# schematic.net
KiCad netlist of a schematic drawn in EAGLE
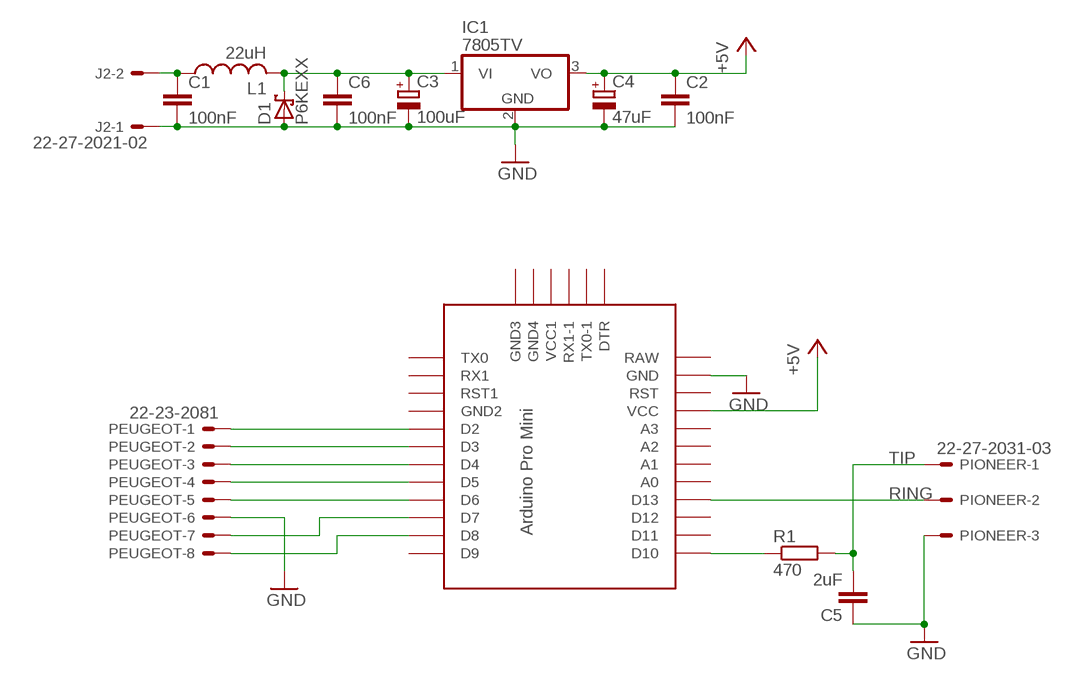
[diagram p0: schematic, sheet 1]

(export (version "E")
  (design (tool "Eeschema 10.0.6"))
  (components
    (comp (ref "C1")
      (value "100nF")
      (footprint "eagle-import:C025-024X044")
      (libsource (lib "eagle-import") (part "C-EU025-024X044"))
    )
    (comp (ref "C2")
      (value "100nF")
      (footprint "eagle-import:C025-024X044")
      (libsource (lib "eagle-import") (part "C-EU025-024X044"))
    )
    (comp (ref "C3")
      (value "100uF")
      (footprint "eagle-import:085CS_1AR")
      (libsource (lib "eagle-import") (part "CPOL-EU085CS-1AR"))
    )
    (comp (ref "C4")
      (value "47uF")
      (footprint "eagle-import:085CS_1AR")
      (libsource (lib "eagle-import") (part "CPOL-EU085CS-1AR"))
    )
    (comp (ref "C5")
      (value "2uF")
      (footprint "eagle-import:C025-024X044")
      (libsource (lib "eagle-import") (part "C-EU025-024X044"))
    )
    (comp (ref "C6")
      (value "100nF")
      (footprint "eagle-import:C025-024X044")
      (libsource (lib "eagle-import") (part "C-EU025-024X044"))
    )
    (comp (ref "D1")
      (value "P6KEXX")
      (footprint "eagle-import:CB417-15")
      (libsource (lib "eagle-import") (part "P6KEXX"))
    )
    (comp (ref "IC1")
      (value "7805TV")
      (footprint "eagle-import:TO220V")
      (libsource (lib "eagle-import") (part "78TV05"))
    )
    (comp (ref "J2")
      (value "22-27-2021-02")
      (footprint "eagle-import:6410-02")
      (libsource (lib "eagle-import") (part "22-?-0227-2021"))
    )
    (comp (ref "L1")
      (value "22uH")
      (footprint "eagle-import:0204_5")
      (libsource (lib "eagle-import") (part "L-US0204/5"))
    )
    (comp (ref "PEUGEOT")
      (value "22-23-2081")
      (footprint "eagle-import:22-23-2081")
      (fields (field (name "MF") "MOLEX"))
      (libsource (lib "eagle-import") (part "22-23-2081"))
    )
    (comp (ref "PIONEER")
      (value "22-27-2031-03")
      (footprint "eagle-import:6410-03")
      (libsource (lib "eagle-import") (part "22-?-0327-2031"))
    )
    (comp (ref "R1")
      (value "470")
      (footprint "eagle-import:0204V")
      (libsource (lib "eagle-import") (part "R-EU_0204/2V"))
    )
    (comp (ref "U$3")
      (value "PRO-MINI-2")
      (footprint "eagle-import:PRO-MINI-2")
      (libsource (lib "eagle-import") (part "PRO-MINI-2"))
    )
  )
  (nets
    (net (code "1") (name "+5V") (class "Default")
      (node (ref "C2") (pin "1") (pinfunction "1_1") (pintype "passive"))
      (node (ref "C4") (pin "+") (pinfunction "+_+") (pintype "passive"))
      (node (ref "IC1") (pin "3") (pinfunction "VO_3") (pintype "passive"))
      (node (ref "U$3") (pin "VCC") (pinfunction "VCC_VCC") (pintype "bidirectional"))
    )
    (net (code "2") (name "/RING") (class "Default")
      (node (ref "PIONEER") (pin "2") (pinfunction "S_2") (pintype "passive"))
      (node (ref "U$3") (pin "D13") (pinfunction "D13_D13") (pintype "bidirectional"))
    )
    (net (code "3") (name "/TIP") (class "Default")
      (node (ref "C5") (pin "2") (pinfunction "2_2") (pintype "passive"))
      (node (ref "PIONEER") (pin "1") (pinfunction "S_1") (pintype "passive"))
      (node (ref "R1") (pin "2") (pinfunction "2_2") (pintype "passive"))
    )
    (net (code "4") (name "GND") (class "Default")
      (node (ref "C1") (pin "2") (pinfunction "2_2") (pintype "passive"))
      (node (ref "C2") (pin "2") (pinfunction "2_2") (pintype "passive"))
      (node (ref "C3") (pin "-") (pinfunction "-_-") (pintype "passive"))
      (node (ref "C4") (pin "-") (pinfunction "-_-") (pintype "passive"))
      (node (ref "C5") (pin "1") (pinfunction "1_1") (pintype "passive"))
      (node (ref "C6") (pin "2") (pinfunction "2_2") (pintype "passive"))
      (node (ref "D1") (pin "A") (pinfunction "A_A") (pintype "passive"))
      (node (ref "IC1") (pin "2") (pinfunction "GND_2") (pintype "passive"))
      (node (ref "J2") (pin "1") (pinfunction "S_1") (pintype "passive"))
      (node (ref "PEUGEOT") (pin "6") (pinfunction "S_6") (pintype "passive"))
      (node (ref "PIONEER") (pin "3") (pinfunction "S_3") (pintype "passive"))
      (node (ref "U$3") (pin "GND") (pinfunction "GND_GND") (pintype "bidirectional"))
    )
    (net (code "5") (name "Net-(IC1-VI)") (class "Default")
      (node (ref "C3") (pin "+") (pinfunction "+_+") (pintype "passive"))
      (node (ref "C6") (pin "1") (pinfunction "1_1") (pintype "passive"))
      (node (ref "D1") (pin "C") (pinfunction "C_C") (pintype "passive"))
      (node (ref "IC1") (pin "1") (pinfunction "VI_1") (pintype "input"))
      (node (ref "L1") (pin "2") (pinfunction "2_2") (pintype "passive"))
    )
    (net (code "6") (name "Net-(J2B-S)") (class "Default")
      (node (ref "C1") (pin "1") (pinfunction "1_1") (pintype "passive"))
      (node (ref "J2") (pin "2") (pinfunction "S_2") (pintype "passive"))
      (node (ref "L1") (pin "1") (pinfunction "1_1") (pintype "passive"))
    )
    (net (code "7") (name "Net-(PEUGEOTA-S)") (class "Default")
      (node (ref "PEUGEOT") (pin "1") (pinfunction "S_1") (pintype "passive"))
      (node (ref "U$3") (pin "D2") (pinfunction "D2_D2") (pintype "bidirectional"))
    )
    (net (code "8") (name "Net-(PEUGEOTB-S)") (class "Default")
      (node (ref "PEUGEOT") (pin "2") (pinfunction "S_2") (pintype "passive"))
      (node (ref "U$3") (pin "D3") (pinfunction "D3_D3") (pintype "bidirectional"))
    )
    (net (code "9") (name "Net-(PEUGEOTC-S)") (class "Default")
      (node (ref "PEUGEOT") (pin "3") (pinfunction "S_3") (pintype "passive"))
      (node (ref "U$3") (pin "D4") (pinfunction "D4_D4") (pintype "bidirectional"))
    )
    (net (code "10") (name "Net-(PEUGEOTD-S)") (class "Default")
      (node (ref "PEUGEOT") (pin "4") (pinfunction "S_4") (pintype "passive"))
      (node (ref "U$3") (pin "D5") (pinfunction "D5_D5") (pintype "bidirectional"))
    )
    (net (code "11") (name "Net-(PEUGEOTE-S)") (class "Default")
      (node (ref "PEUGEOT") (pin "5") (pinfunction "S_5") (pintype "passive"))
      (node (ref "U$3") (pin "D6") (pinfunction "D6_D6") (pintype "bidirectional"))
    )
    (net (code "12") (name "Net-(PEUGEOTG-S)") (class "Default")
      (node (ref "PEUGEOT") (pin "7") (pinfunction "S_7") (pintype "passive"))
      (node (ref "U$3") (pin "D7") (pinfunction "D7_D7") (pintype "bidirectional"))
    )
    (net (code "13") (name "Net-(PEUGEOTH-S)") (class "Default")
      (node (ref "PEUGEOT") (pin "8") (pinfunction "S_8") (pintype "passive"))
      (node (ref "U$3") (pin "D8") (pinfunction "D8_D8") (pintype "bidirectional"))
    )
    (net (code "14") (name "Net-(R1-Pad1)") (class "Default")
      (node (ref "R1") (pin "1") (pinfunction "1_1") (pintype "passive"))
      (node (ref "U$3") (pin "D10") (pinfunction "D10_D10") (pintype "bidirectional"))
    )
    (net (code "15") (name "unconnected-(U$3-GND2-PadGND1)") (class "Default")
      (node (ref "U$3") (pin "GND1") (pinfunction "GND2_GND1") (pintype "bidirectional"))
    )
    (net (code "16") (name "unconnected-(U$3-GND3-PadGND2)") (class "Default")
      (node (ref "U$3") (pin "GND2") (pinfunction "GND3_GND2") (pintype "bidirectional"))
    )
    (net (code "17") (name "unconnected-(U$3-GND4-PadGND3)") (class "Default")
      (node (ref "U$3") (pin "GND3") (pinfunction "GND4_GND3") (pintype "bidirectional"))
    )
    (net (code "18") (name "unconnected-(U$3-PadA0)") (class "Default")
      (node (ref "U$3") (pin "A0") (pinfunction "A0_A0") (pintype "bidirectional"))
    )
    (net (code "19") (name "unconnected-(U$3-PadA1)") (class "Default")
      (node (ref "U$3") (pin "A1") (pinfunction "A1_A1") (pintype "bidirectional"))
    )
    (net (code "20") (name "unconnected-(U$3-PadA2)") (class "Default")
      (node (ref "U$3") (pin "A2") (pinfunction "A2_A2") (pintype "bidirectional"))
    )
    (net (code "21") (name "unconnected-(U$3-PadA3)") (class "Default")
      (node (ref "U$3") (pin "A3") (pinfunction "A3_A3") (pintype "bidirectional"))
    )
    (net (code "22") (name "unconnected-(U$3-PadD9)") (class "Default")
      (node (ref "U$3") (pin "D9") (pinfunction "D9_D9") (pintype "bidirectional"))
    )
    (net (code "23") (name "unconnected-(U$3-PadD11)") (class "Default")
      (node (ref "U$3") (pin "D11") (pinfunction "D11_D11") (pintype "bidirectional"))
    )
    (net (code "24") (name "unconnected-(U$3-PadD12)") (class "Default")
      (node (ref "U$3") (pin "D12") (pinfunction "D12_D12") (pintype "bidirectional"))
    )
    (net (code "25") (name "unconnected-(U$3-PadDTR)") (class "Default")
      (node (ref "U$3") (pin "DTR") (pinfunction "DTR_DTR") (pintype "bidirectional"))
    )
    (net (code "26") (name "unconnected-(U$3-PadRAW)") (class "Default")
      (node (ref "U$3") (pin "RAW") (pinfunction "RAW_RAW") (pintype "bidirectional"))
    )
    (net (code "27") (name "unconnected-(U$3-PadRST)") (class "Default")
      (node (ref "U$3") (pin "RST") (pinfunction "RST_RST") (pintype "bidirectional"))
    )
    (net (code "28") (name "unconnected-(U$3-PadRST1)") (class "Default")
      (node (ref "U$3") (pin "RST1") (pinfunction "RST1_RST1") (pintype "bidirectional"))
    )
    (net (code "29") (name "unconnected-(U$3-PadRX1)") (class "Default")
      (node (ref "U$3") (pin "RX1") (pinfunction "RX1_RX1") (pintype "bidirectional"))
    )
    (net (code "30") (name "unconnected-(U$3-PadRX1-1)") (class "Default")
      (node (ref "U$3") (pin "RX1-1") (pinfunction "RX1-1_RX1-1") (pintype "bidirectional"))
    )
    (net (code "31") (name "unconnected-(U$3-PadTX0)") (class "Default")
      (node (ref "U$3") (pin "TX0") (pinfunction "TX0_TX0") (pintype "bidirectional"))
    )
    (net (code "32") (name "unconnected-(U$3-PadTX0-1)") (class "Default")
      (node (ref "U$3") (pin "TX0-1") (pinfunction "TX0-1_TX0-1") (pintype "bidirectional"))
    )
    (net (code "33") (name "unconnected-(U$3-PadVCC1)") (class "Default")
      (node (ref "U$3") (pin "VCC1") (pinfunction "VCC1_VCC1") (pintype "bidirectional"))
    )
  )
)
